# data_proV3.net
KiCad netlist of a schematic drawn in EAGLE
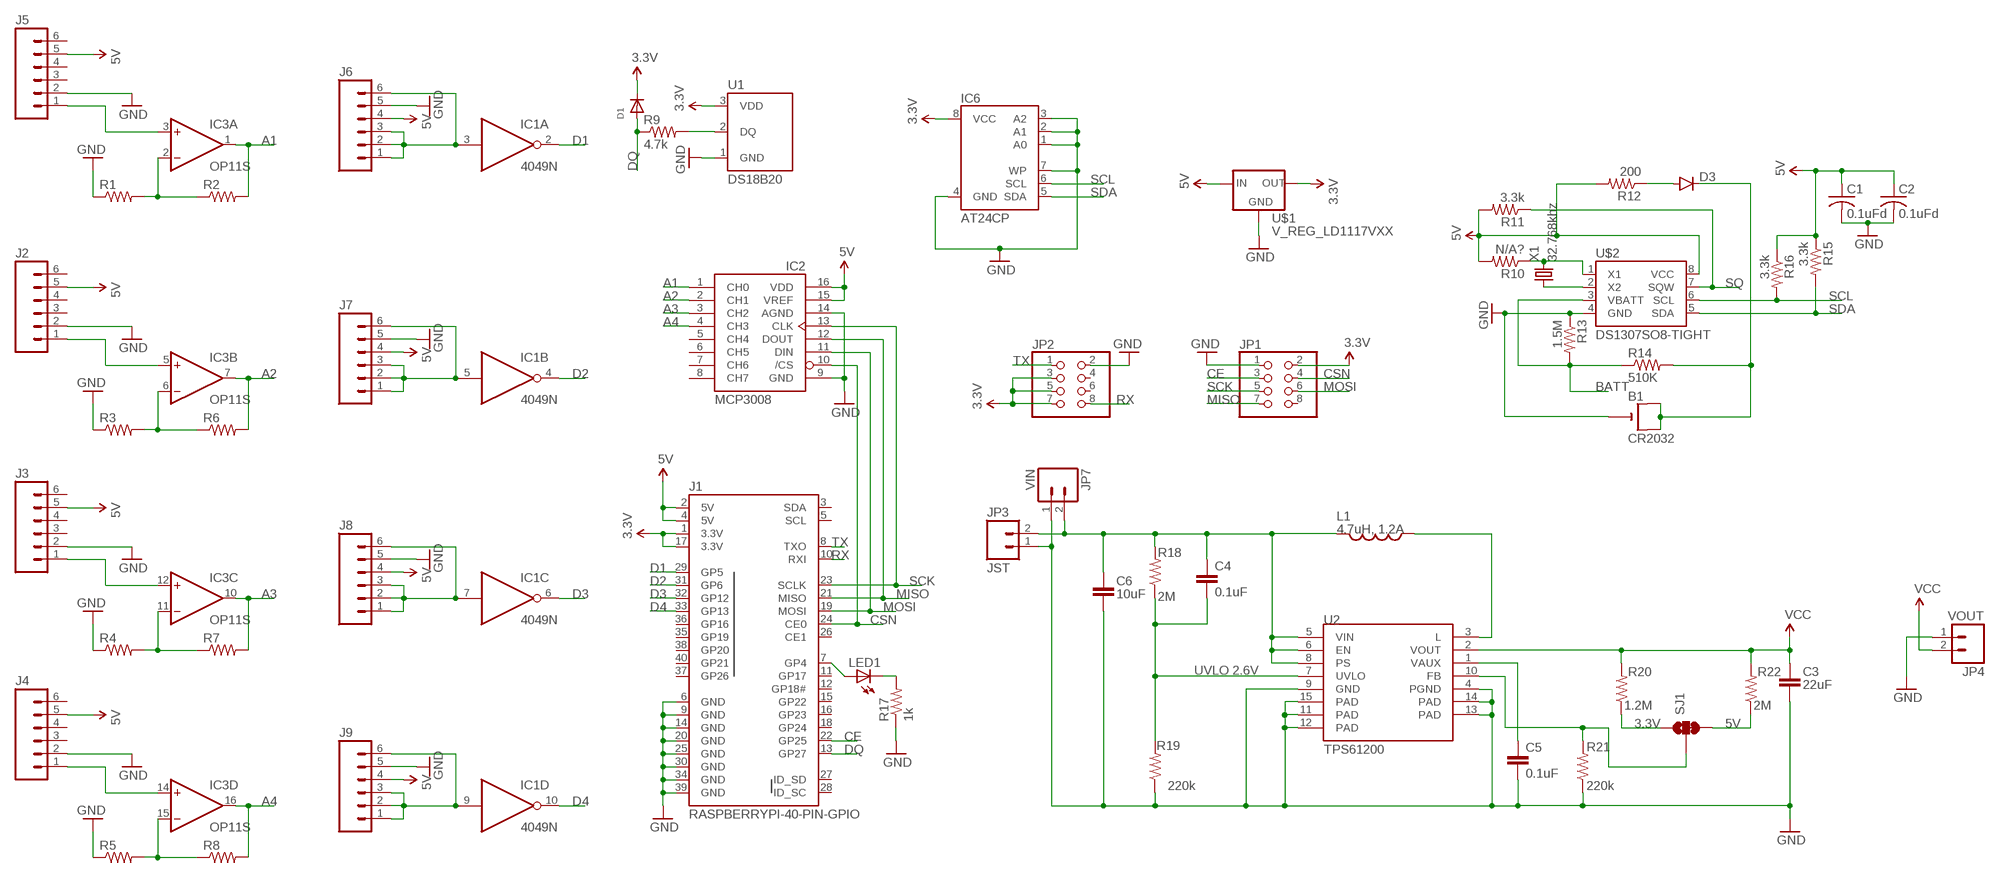
[diagram p0: schematic, sheet 1]

(export (version "E")
  (design (tool "Eeschema 10.0.6"))
  (components
    (comp (ref "B1")
      (value "CR2032")
      (footprint "eagle-import:CR2032-SMD")
      (libsource (lib "eagle-import") (part "CR2032SMT"))
    )
    (comp (ref "C1")
      (value "0.1uFd")
      (footprint "eagle-import:C0805")
      (libsource (lib "eagle-import") (part "C-USC0805"))
    )
    (comp (ref "C2")
      (value "0.1uFd")
      (footprint "eagle-import:C0805")
      (libsource (lib "eagle-import") (part "C-USC0805"))
    )
    (comp (ref "C3")
      (value "22uF")
      (footprint "eagle-import:0805")
      (libsource (lib "eagle-import") (part "CAP0805"))
    )
    (comp (ref "C4")
      (value "0.1uF")
      (footprint "eagle-import:0603-CAP")
      (libsource (lib "eagle-import") (part "CAP0603-CAP"))
    )
    (comp (ref "C5")
      (value "0.1uF")
      (footprint "eagle-import:0603-CAP")
      (libsource (lib "eagle-import") (part "CAP0603-CAP"))
    )
    (comp (ref "C6")
      (value "10uF")
      (footprint "eagle-import:1206")
      (libsource (lib "eagle-import") (part "CAP1206"))
    )
    (comp (ref "D1")
      (value "DIODESOD-323F")
      (footprint "eagle-import:SOD-323F")
      (libsource (lib "eagle-import") (part "DIODESOD-323F"))
    )
    (comp (ref "D3")
      (value "DIODESMB")
      (footprint "eagle-import:SMB-DIODE")
      (libsource (lib "eagle-import") (part "DIODESMB"))
    )
    (comp (ref "IC1")
      (value "4049N")
      (footprint "eagle-import:DIL16")
      (libsource (lib "eagle-import") (part "4049N"))
    )
    (comp (ref "IC2")
      (value "MCP3008")
      (footprint "eagle-import:DIL16")
      (libsource (lib "eagle-import") (part "MCP3008"))
    )
    (comp (ref "IC3")
      (value "OP11S")
      (footprint "eagle-import:DIL16")
      (libsource (lib "eagle-import") (part "OP11S"))
    )
    (comp (ref "IC6")
      (value "AT24CP")
      (footprint "eagle-import:DIL08")
      (fields (field (name "MPN") "AT24C1024BW-SH-B"))
      (libsource (lib "eagle-import") (part "AT24CP"))
    )
    (comp (ref "J1")
      (value "RASPBERRYPI-40-PIN-GPIO")
      (footprint "eagle-import:2X20-SHROUDED")
      (libsource (lib "eagle-import") (part "RASPBERRYPI-40-PIN-GPIO"))
    )
    (comp (ref "J2")
      (value "M06VERNIER-ANALOG")
      (footprint "eagle-import:BTA")
      (libsource (lib "eagle-import") (part "M06VERNIER-ANALOG"))
    )
    (comp (ref "J3")
      (value "M06VERNIER-ANALOG")
      (footprint "eagle-import:BTA")
      (libsource (lib "eagle-import") (part "M06VERNIER-ANALOG"))
    )
    (comp (ref "J4")
      (value "M06VERNIER-ANALOG")
      (footprint "eagle-import:BTA")
      (libsource (lib "eagle-import") (part "M06VERNIER-ANALOG"))
    )
    (comp (ref "J5")
      (value "M06VERNIER-ANALOG")
      (footprint "eagle-import:BTA")
      (libsource (lib "eagle-import") (part "M06VERNIER-ANALOG"))
    )
    (comp (ref "J6")
      (value "M06VERNIER-DIGITAL")
      (footprint "eagle-import:BTD")
      (libsource (lib "eagle-import") (part "M06VERNIER-DIGITAL"))
    )
    (comp (ref "J7")
      (value "M06VERNIER-DIGITAL")
      (footprint "eagle-import:BTD")
      (libsource (lib "eagle-import") (part "M06VERNIER-DIGITAL"))
    )
    (comp (ref "J8")
      (value "M06VERNIER-DIGITAL")
      (footprint "eagle-import:BTD")
      (libsource (lib "eagle-import") (part "M06VERNIER-DIGITAL"))
    )
    (comp (ref "J9")
      (value "M06VERNIER-DIGITAL")
      (footprint "eagle-import:BTD")
      (libsource (lib "eagle-import") (part "M06VERNIER-DIGITAL"))
    )
    (comp (ref "JP1")
      (value "PINHD-2X4")
      (footprint "eagle-import:2X04")
      (libsource (lib "eagle-import") (part "pinhead_PINHD-2X4"))
    )
    (comp (ref "JP2")
      (value "PINHD-2X4")
      (footprint "eagle-import:2X04")
      (libsource (lib "eagle-import") (part "PINHD-2X4"))
    )
    (comp (ref "JP3")
      (value "JST")
      (footprint "eagle-import:JST-2-SMD")
      (libsource (lib "eagle-import") (part "M02-JST-2MM-SMT"))
    )
    (comp (ref "JP4")
      (value "VOUT")
      (footprint "eagle-import:1X02")
      (libsource (lib "eagle-import") (part "M02PTH"))
    )
    (comp (ref "JP7")
      (value "VIN")
      (footprint "eagle-import:1X02")
      (libsource (lib "eagle-import") (part "M02PTH"))
    )
    (comp (ref "L1")
      (value "4.7uH, 1.2A")
      (footprint "eagle-import:CDRH2D09")
      (libsource (lib "eagle-import") (part "INDUCTOR."))
    )
    (comp (ref "LED1")
      (value "LEDCHIP-LED0805")
      (footprint "eagle-import:CHIP-LED0805")
      (libsource (lib "eagle-import") (part "LEDCHIP-LED0805"))
    )
    (comp (ref "R1")
      (value "R-US_R0805")
      (footprint "eagle-import:R0805")
      (libsource (lib "eagle-import") (part "resistor_R-US_R0805"))
    )
    (comp (ref "R2")
      (value "R-US_R0805")
      (footprint "eagle-import:R0805")
      (libsource (lib "eagle-import") (part "resistor_R-US_R0805"))
    )
    (comp (ref "R3")
      (value "R-US_R0805")
      (footprint "eagle-import:R0805")
      (libsource (lib "eagle-import") (part "resistor_R-US_R0805"))
    )
    (comp (ref "R4")
      (value "R-US_R0805")
      (footprint "eagle-import:R0805")
      (libsource (lib "eagle-import") (part "resistor_R-US_R0805"))
    )
    (comp (ref "R5")
      (value "R-US_R0805")
      (footprint "eagle-import:R0805")
      (libsource (lib "eagle-import") (part "resistor_R-US_R0805"))
    )
    (comp (ref "R6")
      (value "R-US_R0805")
      (footprint "eagle-import:R0805")
      (libsource (lib "eagle-import") (part "resistor_R-US_R0805"))
    )
    (comp (ref "R7")
      (value "R-US_R0805")
      (footprint "eagle-import:R0805")
      (libsource (lib "eagle-import") (part "resistor_R-US_R0805"))
    )
    (comp (ref "R8")
      (value "R-US_R0805")
      (footprint "eagle-import:R0805")
      (libsource (lib "eagle-import") (part "resistor_R-US_R0805"))
    )
    (comp (ref "R9")
      (value "4.7k")
      (footprint "eagle-import:R0805")
      (libsource (lib "eagle-import") (part "resistor_R-US_R0805"))
    )
    (comp (ref "R10")
      (value "N/A?")
      (footprint "eagle-import:R0805")
      (libsource (lib "eagle-import") (part "R-US_R0805"))
    )
    (comp (ref "R11")
      (value "3.3k")
      (footprint "eagle-import:R0805")
      (libsource (lib "eagle-import") (part "R-US_R0805"))
    )
    (comp (ref "R12")
      (value "200")
      (footprint "eagle-import:R0805")
      (libsource (lib "eagle-import") (part "R-US_R0805"))
    )
    (comp (ref "R13")
      (value "1.5M")
      (footprint "eagle-import:R0805")
      (libsource (lib "eagle-import") (part "R-US_R0805"))
    )
    (comp (ref "R14")
      (value "510K")
      (footprint "eagle-import:R0805")
      (libsource (lib "eagle-import") (part "R-US_R0805"))
    )
    (comp (ref "R15")
      (value "3.3k")
      (footprint "eagle-import:R0805")
      (libsource (lib "eagle-import") (part "R-US_R0805"))
    )
    (comp (ref "R16")
      (value "3.3k")
      (footprint "eagle-import:R0805")
      (libsource (lib "eagle-import") (part "R-US_R0805"))
    )
    (comp (ref "R17")
      (value "1k")
      (footprint "eagle-import:R0805")
      (libsource (lib "eagle-import") (part "R-US_R0805"))
    )
    (comp (ref "R18")
      (value "2M")
      (footprint "eagle-import:0603-RES")
      (libsource (lib "eagle-import") (part "RESISTOR0603-RES"))
    )
    (comp (ref "R19")
      (value "220k")
      (footprint "eagle-import:0603-RES")
      (libsource (lib "eagle-import") (part "RESISTOR0603-RES"))
    )
    (comp (ref "R20")
      (value "1.2M")
      (footprint "eagle-import:0603-RES")
      (libsource (lib "eagle-import") (part "RESISTOR0603-RES"))
    )
    (comp (ref "R21")
      (value "220k")
      (footprint "eagle-import:0603-RES")
      (libsource (lib "eagle-import") (part "RESISTOR0603-RES"))
    )
    (comp (ref "R22")
      (value "2M")
      (footprint "eagle-import:0603-RES")
      (libsource (lib "eagle-import") (part "RESISTOR0603-RES"))
    )
    (comp (ref "SJ1")
      (value "SOLDERJUMPER_2WAYPASTE2&3")
      (footprint "eagle-import:SJ_3_PASTE2&3")
      (libsource (lib "eagle-import") (part "SOLDERJUMPER_2WAYPASTE2&3"))
    )
    (comp (ref "U$1")
      (value "V_REG_LD1117VXX")
      (footprint "eagle-import:78XXL")
      (libsource (lib "eagle-import") (part "V_REG_LD1117VXX"))
    )
    (comp (ref "U$2")
      (value "DS1307SO8-TIGHT")
      (footprint "eagle-import:SO08-TIGHT")
      (libsource (lib "eagle-import") (part "DS1307SO8-TIGHT"))
    )
    (comp (ref "U1")
      (value "DS18B20")
      (footprint "eagle-import:TO-92-AMMO")
      (libsource (lib "eagle-import") (part "DS18B20"))
    )
    (comp (ref "U2")
      (value "TPS61200")
      (footprint "eagle-import:QFN-10_PAD")
      (libsource (lib "eagle-import") (part "TPS61200"))
    )
    (comp (ref "X1")
      (value "32.768khz")
      (footprint "eagle-import:TC38H")
      (libsource (lib "eagle-import") (part "CRYSTALTC38H"))
    )
  )
  (nets
    (net (code "1") (name "/A1") (class "Default")
      (node (ref "IC2") (pin "1") (pinfunction "CH0_1") (pintype "input"))
      (node (ref "IC3") (pin "1") (pinfunction "OUT_1") (pintype "output"))
      (node (ref "R2") (pin "2") (pinfunction "2_2") (pintype "passive"))
    )
    (net (code "2") (name "/A2") (class "Default")
      (node (ref "IC2") (pin "2") (pinfunction "CH1_2") (pintype "input"))
      (node (ref "IC3") (pin "7") (pinfunction "OUT_7") (pintype "output"))
      (node (ref "R6") (pin "2") (pinfunction "2_2") (pintype "passive"))
    )
    (net (code "3") (name "/A3") (class "Default")
      (node (ref "IC2") (pin "3") (pinfunction "CH2_3") (pintype "input"))
      (node (ref "IC3") (pin "10") (pinfunction "OUT_10") (pintype "output"))
      (node (ref "R7") (pin "2") (pinfunction "2_2") (pintype "passive"))
    )
    (net (code "4") (name "/A4") (class "Default")
      (node (ref "IC2") (pin "4") (pinfunction "CH3_4") (pintype "input"))
      (node (ref "IC3") (pin "16") (pinfunction "OUT_16") (pintype "output"))
      (node (ref "R8") (pin "2") (pinfunction "2_2") (pintype "passive"))
    )
    (net (code "5") (name "/BATT") (class "Default")
      (node (ref "R13") (pin "2") (pinfunction "2_2") (pintype "passive"))
      (node (ref "R14") (pin "1") (pinfunction "1_1") (pintype "passive"))
      (node (ref "U$2") (pin "3") (pinfunction "VBATT_3") (pintype "bidirectional"))
    )
    (net (code "6") (name "/CE") (class "Default")
      (node (ref "J1") (pin "22") (pinfunction "GP25_22") (pintype "bidirectional"))
      (node (ref "JP1") (pin "3") (pinfunction "3_3") (pintype "passive"))
    )
    (net (code "7") (name "/CSN") (class "Default")
      (node (ref "IC2") (pin "10") (pinfunction "/CS_10") (pintype "input"))
      (node (ref "J1") (pin "24") (pinfunction "CE0_24") (pintype "output"))
      (node (ref "JP1") (pin "4") (pinfunction "4_4") (pintype "passive"))
    )
    (net (code "8") (name "/D1") (class "Default")
      (node (ref "IC1") (pin "2") (pinfunction "O_2") (pintype "output"))
      (node (ref "J1") (pin "29") (pinfunction "GP5_29") (pintype "bidirectional"))
    )
    (net (code "9") (name "/D2") (class "Default")
      (node (ref "IC1") (pin "4") (pinfunction "O_4") (pintype "output"))
      (node (ref "J1") (pin "31") (pinfunction "GP6_31") (pintype "bidirectional"))
    )
    (net (code "10") (name "/D3") (class "Default")
      (node (ref "IC1") (pin "6") (pinfunction "O_6") (pintype "output"))
      (node (ref "J1") (pin "32") (pinfunction "GP12_32") (pintype "bidirectional"))
    )
    (net (code "11") (name "/D4") (class "Default")
      (node (ref "IC1") (pin "10") (pinfunction "O_10") (pintype "output"))
      (node (ref "J1") (pin "33") (pinfunction "GP13_33") (pintype "bidirectional"))
    )
    (net (code "12") (name "/DQ") (class "Default")
      (node (ref "D1") (pin "A") (pinfunction "A_A") (pintype "passive"))
      (node (ref "J1") (pin "13") (pinfunction "GP27_13") (pintype "bidirectional"))
      (node (ref "R9") (pin "1") (pinfunction "1_1") (pintype "passive"))
    )
    (net (code "13") (name "/MISO") (class "Default")
      (node (ref "IC2") (pin "12") (pinfunction "DOUT_12") (pintype "output"))
      (node (ref "J1") (pin "21") (pinfunction "MISO_21") (pintype "input"))
      (node (ref "JP1") (pin "7") (pinfunction "7_7") (pintype "passive"))
    )
    (net (code "14") (name "/MOSI") (class "Default")
      (node (ref "IC2") (pin "11") (pinfunction "DIN_11") (pintype "input"))
      (node (ref "J1") (pin "19") (pinfunction "MOSI_19") (pintype "output"))
      (node (ref "JP1") (pin "6") (pinfunction "6_6") (pintype "passive"))
    )
    (net (code "15") (name "/RX") (class "Default")
      (node (ref "J1") (pin "10") (pinfunction "RXI_10") (pintype "input"))
      (node (ref "JP2") (pin "8") (pinfunction "8_8") (pintype "passive"))
    )
    (net (code "16") (name "/SCK") (class "Default")
      (node (ref "IC2") (pin "13") (pinfunction "CLK_13") (pintype "input"))
      (node (ref "J1") (pin "23") (pinfunction "SCLK_23") (pintype "output"))
      (node (ref "JP1") (pin "5") (pinfunction "5_5") (pintype "passive"))
    )
    (net (code "17") (name "/SCL") (class "Default")
      (node (ref "IC6") (pin "6") (pinfunction "SCL_6") (pintype "bidirectional"))
      (node (ref "R16") (pin "2") (pinfunction "2_2") (pintype "passive"))
      (node (ref "U$2") (pin "6") (pinfunction "SCL_6") (pintype "bidirectional"))
    )
    (net (code "18") (name "/SDA") (class "Default")
      (node (ref "IC6") (pin "5") (pinfunction "SDA_5") (pintype "bidirectional"))
      (node (ref "R15") (pin "2") (pinfunction "2_2") (pintype "passive"))
      (node (ref "U$2") (pin "5") (pinfunction "SDA_5") (pintype "bidirectional"))
    )
    (net (code "19") (name "/SQ") (class "Default")
      (node (ref "R11") (pin "1") (pinfunction "1_1") (pintype "passive"))
      (node (ref "U$2") (pin "7") (pinfunction "SQW_7") (pintype "bidirectional"))
    )
    (net (code "20") (name "/TX") (class "Default")
      (node (ref "J1") (pin "8") (pinfunction "TXO_8") (pintype "output"))
      (node (ref "JP2") (pin "1") (pinfunction "1_1") (pintype "passive"))
    )
    (net (code "21") (name "3.3V") (class "Default")
      (node (ref "D1") (pin "C") (pinfunction "C_C") (pintype "passive"))
      (node (ref "IC6") (pin "8") (pinfunction "VCC_8") (pintype "power_in"))
      (node (ref "J1") (pin "1") (pinfunction "3.3V_1") (pintype "power_in"))
      (node (ref "J1") (pin "17") (pinfunction "3.3V_17") (pintype "power_in"))
      (node (ref "JP1") (pin "2") (pinfunction "2_2") (pintype "passive"))
      (node (ref "JP2") (pin "3") (pinfunction "3_3") (pintype "passive"))
      (node (ref "JP2") (pin "5") (pinfunction "5_5") (pintype "passive"))
      (node (ref "JP2") (pin "7") (pinfunction "7_7") (pintype "passive"))
      (node (ref "R20") (pin "1") (pinfunction "1_1") (pintype "passive"))
      (node (ref "SJ1") (pin "1") (pinfunction "1_1") (pintype "passive"))
      (node (ref "U$1") (pin "GND") (pinfunction "OUT_GND") (pintype "passive"))
      (node (ref "U1") (pin "3") (pinfunction "VDD_3") (pintype "power_in"))
    )
    (net (code "22") (name "5V") (class "Default")
      (node (ref "C1") (pin "1") (pinfunction "1_1") (pintype "passive"))
      (node (ref "C2") (pin "1") (pinfunction "1_1") (pintype "passive"))
      (node (ref "IC2") (pin "15") (pinfunction "VREF_15") (pintype "input"))
      (node (ref "IC2") (pin "16") (pinfunction "VDD_16") (pintype "power_in"))
      (node (ref "J1") (pin "2") (pinfunction "5V_2") (pintype "power_in"))
      (node (ref "J1") (pin "4") (pinfunction "5V_4") (pintype "power_in"))
      (node (ref "J2") (pin "5") (pinfunction "5_5") (pintype "passive"))
      (node (ref "J3") (pin "5") (pinfunction "5_5") (pintype "passive"))
      (node (ref "J4") (pin "5") (pinfunction "5_5") (pintype "passive"))
      (node (ref "J5") (pin "5") (pinfunction "5_5") (pintype "passive"))
      (node (ref "J6") (pin "4") (pinfunction "4_4") (pintype "passive"))
      (node (ref "J7") (pin "4") (pinfunction "4_4") (pintype "passive"))
      (node (ref "J8") (pin "4") (pinfunction "4_4") (pintype "passive"))
      (node (ref "J9") (pin "4") (pinfunction "4_4") (pintype "passive"))
      (node (ref "R10") (pin "2") (pinfunction "2_2") (pintype "passive"))
      (node (ref "R11") (pin "2") (pinfunction "2_2") (pintype "passive"))
      (node (ref "R12") (pin "2") (pinfunction "2_2") (pintype "passive"))
      (node (ref "R15") (pin "1") (pinfunction "1_1") (pintype "passive"))
      (node (ref "R16") (pin "1") (pinfunction "1_1") (pintype "passive"))
      (node (ref "R22") (pin "1") (pinfunction "1_1") (pintype "passive"))
      (node (ref "SJ1") (pin "3") (pinfunction "3_3") (pintype "passive"))
      (node (ref "U$1") (pin "OUT") (pinfunction "IN_OUT") (pintype "input"))
      (node (ref "U$2") (pin "8") (pinfunction "VCC_8") (pintype "bidirectional"))
    )
    (net (code "23") (name "GND") (class "Default")
      (node (ref "B1") (pin "-") (pinfunction "-_-") (pintype "passive"))
      (node (ref "C1") (pin "2") (pinfunction "2_2") (pintype "passive"))
      (node (ref "C2") (pin "2") (pinfunction "2_2") (pintype "passive"))
      (node (ref "C3") (pin "2") (pinfunction "2_2") (pintype "passive"))
      (node (ref "C5") (pin "2") (pinfunction "2_2") (pintype "passive"))
      (node (ref "C6") (pin "2") (pinfunction "2_2") (pintype "passive"))
      (node (ref "IC2") (pin "14") (pinfunction "AGND_14") (pintype "power_in"))
      (node (ref "IC2") (pin "9") (pinfunction "GND_9") (pintype "power_in"))
      (node (ref "IC6") (pin "1") (pinfunction "A0_1") (pintype "input"))
      (node (ref "IC6") (pin "2") (pinfunction "A1_2") (pintype "input"))
      (node (ref "IC6") (pin "3") (pinfunction "A2_3") (pintype "input"))
      (node (ref "IC6") (pin "4") (pinfunction "GND_4") (pintype "power_in"))
      (node (ref "IC6") (pin "7") (pinfunction "WP_7") (pintype "input"))
      (node (ref "J1") (pin "14") (pinfunction "GND_14") (pintype "power_in"))
      (node (ref "J1") (pin "20") (pinfunction "GND_20") (pintype "power_in"))
      (node (ref "J1") (pin "25") (pinfunction "GND_25") (pintype "power_in"))
      (node (ref "J1") (pin "30") (pinfunction "GND_30") (pintype "power_in"))
      (node (ref "J1") (pin "34") (pinfunction "GND_34") (pintype "power_in"))
      (node (ref "J1") (pin "39") (pinfunction "GND_39") (pintype "power_in"))
      (node (ref "J1") (pin "6") (pinfunction "GND_6") (pintype "power_in"))
      (node (ref "J1") (pin "9") (pinfunction "GND_9") (pintype "power_in"))
      (node (ref "J2") (pin "2") (pinfunction "2_2") (pintype "passive"))
      (node (ref "J3") (pin "2") (pinfunction "2_2") (pintype "passive"))
      (node (ref "J4") (pin "2") (pinfunction "2_2") (pintype "passive"))
      (node (ref "J5") (pin "2") (pinfunction "2_2") (pintype "passive"))
      (node (ref "J6") (pin "5") (pinfunction "5_5") (pintype "passive"))
      (node (ref "J7") (pin "5") (pinfunction "5_5") (pintype "passive"))
      (node (ref "J8") (pin "5") (pinfunction "5_5") (pintype "passive"))
      (node (ref "J9") (pin "5") (pinfunction "5_5") (pintype "passive"))
      (node (ref "JP1") (pin "1") (pinfunction "1_1") (pintype "passive"))
      (node (ref "JP2") (pin "2") (pinfunction "2_2") (pintype "passive"))
      (node (ref "JP3") (pin "1") (pinfunction "1_1") (pintype "passive"))
      (node (ref "JP4") (pin "1") (pinfunction "1_1") (pintype "passive"))
      (node (ref "JP7") (pin "1") (pinfunction "1_1") (pintype "passive"))
      (node (ref "R1") (pin "1") (pinfunction "1_1") (pintype "passive"))
      (node (ref "R13") (pin "1") (pinfunction "1_1") (pintype "passive"))
      (node (ref "R17") (pin "1") (pinfunction "1_1") (pintype "passive"))
      (node (ref "R19") (pin "1") (pinfunction "1_1") (pintype "passive"))
      (node (ref "R21") (pin "1") (pinfunction "1_1") (pintype "passive"))
      (node (ref "R3") (pin "1") (pinfunction "1_1") (pintype "passive"))
      (node (ref "R4") (pin "1") (pinfunction "1_1") (pintype "passive"))
      (node (ref "R5") (pin "1") (pinfunction "1_1") (pintype "passive"))
      (node (ref "U$1") (pin "IN") (pinfunction "GND_IN") (pintype "input"))
      (node (ref "U$2") (pin "4") (pinfunction "GND_4") (pintype "bidirectional"))
      (node (ref "U1") (pin "1") (pinfunction "GND_1") (pintype "power_in"))
      (node (ref "U2") (pin "11") (pinfunction "PAD_11") (pintype "power_in"))
      (node (ref "U2") (pin "12") (pinfunction "PAD_12") (pintype "power_in"))
      (node (ref "U2") (pin "13") (pinfunction "PAD_13") (pintype "power_in"))
      (node (ref "U2") (pin "14") (pinfunction "PAD_14") (pintype "power_in"))
      (node (ref "U2") (pin "15") (pinfunction "PAD_15") (pintype "power_in"))
      (node (ref "U2") (pin "4") (pinfunction "PGND_4") (pintype "power_in"))
      (node (ref "U2") (pin "9") (pinfunction "GND_9") (pintype "power_in"))
    )
    (net (code "24") (name "Net-(B1-+)") (class "Default")
      (node (ref "B1") (pin "+$1") (pinfunction "+_+$1") (pintype "passive"))
      (node (ref "B1") (pin "+$2") (pinfunction "+1_+$2") (pintype "passive"))
      (node (ref "D3") (pin "C") (pinfunction "C_C") (pintype "passive"))
      (node (ref "R14") (pin "2") (pinfunction "2_2") (pintype "passive"))
    )
    (net (code "25") (name "Net-(D3-PadA)") (class "Default")
      (node (ref "D3") (pin "A") (pinfunction "A_A") (pintype "passive"))
      (node (ref "R12") (pin "1") (pinfunction "1_1") (pintype "passive"))
    )
    (net (code "26") (name "Net-(IC1A-I)") (class "Default")
      (node (ref "IC1") (pin "3") (pinfunction "I_3") (pintype "input"))
      (node (ref "J6") (pin "1") (pinfunction "1_1") (pintype "passive"))
      (node (ref "J6") (pin "2") (pinfunction "2_2") (pintype "passive"))
      (node (ref "J6") (pin "3") (pinfunction "3_3") (pintype "passive"))
      (node (ref "J6") (pin "6") (pinfunction "6_6") (pintype "passive"))
    )
    (net (code "27") (name "Net-(IC1B-I)") (class "Default")
      (node (ref "IC1") (pin "5") (pinfunction "I_5") (pintype "input"))
      (node (ref "J7") (pin "1") (pinfunction "1_1") (pintype "passive"))
      (node (ref "J7") (pin "2") (pinfunction "2_2") (pintype "passive"))
      (node (ref "J7") (pin "3") (pinfunction "3_3") (pintype "passive"))
      (node (ref "J7") (pin "6") (pinfunction "6_6") (pintype "passive"))
    )
    (net (code "28") (name "Net-(IC1C-I)") (class "Default")
      (node (ref "IC1") (pin "7") (pinfunction "I_7") (pintype "input"))
      (node (ref "J8") (pin "1") (pinfunction "1_1") (pintype "passive"))
      (node (ref "J8") (pin "2") (pinfunction "2_2") (pintype "passive"))
      (node (ref "J8") (pin "3") (pinfunction "3_3") (pintype "passive"))
      (node (ref "J8") (pin "6") (pinfunction "6_6") (pintype "passive"))
    )
    (net (code "29") (name "Net-(IC1D-I)") (class "Default")
      (node (ref "IC1") (pin "9") (pinfunction "I_9") (pintype "input"))
      (node (ref "J9") (pin "1") (pinfunction "1_1") (pintype "passive"))
      (node (ref "J9") (pin "2") (pinfunction "2_2") (pintype "passive"))
      (node (ref "J9") (pin "3") (pinfunction "3_3") (pintype "passive"))
      (node (ref "J9") (pin "6") (pinfunction "6_6") (pintype "passive"))
    )
    (net (code "30") (name "Net-(IC3A-+IN)") (class "Default")
      (node (ref "IC3") (pin "3") (pinfunction "+IN_3") (pintype "input"))
      (node (ref "J5") (pin "1") (pinfunction "1_1") (pintype "passive"))
    )
    (net (code "31") (name "Net-(IC3A--IN)") (class "Default")
      (node (ref "IC3") (pin "2") (pinfunction "-IN_2") (pintype "input"))
      (node (ref "R1") (pin "2") (pinfunction "2_2") (pintype "passive"))
      (node (ref "R2") (pin "1") (pinfunction "1_1") (pintype "passive"))
    )
    (net (code "32") (name "Net-(IC3B-+IN)") (class "Default")
      (node (ref "IC3") (pin "5") (pinfunction "+IN_5") (pintype "input"))
      (node (ref "J2") (pin "1") (pinfunction "1_1") (pintype "passive"))
    )
    (net (code "33") (name "Net-(IC3B--IN)") (class "Default")
      (node (ref "IC3") (pin "6") (pinfunction "-IN_6") (pintype "input"))
      (node (ref "R3") (pin "2") (pinfunction "2_2") (pintype "passive"))
      (node (ref "R6") (pin "1") (pinfunction "1_1") (pintype "passive"))
    )
    (net (code "34") (name "Net-(IC3C-+IN)") (class "Default")
      (node (ref "IC3") (pin "12") (pinfunction "+IN_12") (pintype "input"))
      (node (ref "J3") (pin "1") (pinfunction "1_1") (pintype "passive"))
    )
    (net (code "35") (name "Net-(IC3C--IN)") (class "Default")
      (node (ref "IC3") (pin "11") (pinfunction "-IN_11") (pintype "input"))
      (node (ref "R4") (pin "2") (pinfunction "2_2") (pintype "passive"))
      (node (ref "R7") (pin "1") (pinfunction "1_1") (pintype "passive"))
    )
    (net (code "36") (name "Net-(IC3D-+IN)") (class "Default")
      (node (ref "IC3") (pin "14") (pinfunction "+IN_14") (pintype "input"))
      (node (ref "J4") (pin "1") (pinfunction "1_1") (pintype "passive"))
    )
    (net (code "37") (name "Net-(IC3D--IN)") (class "Default")
      (node (ref "IC3") (pin "15") (pinfunction "-IN_15") (pintype "input"))
      (node (ref "R5") (pin "2") (pinfunction "2_2") (pintype "passive"))
      (node (ref "R8") (pin "1") (pinfunction "1_1") (pintype "passive"))
    )
    (net (code "38") (name "Net-(J1-GP4)") (class "Default")
      (node (ref "J1") (pin "7") (pinfunction "GP4_7") (pintype "bidirectional"))
      (node (ref "LED1") (pin "A") (pinfunction "A_A") (pintype "passive"))
    )
    (net (code "39") (name "Net-(L1-1)") (class "Default")
      (node (ref "L1") (pin "P$1") (pinfunction "1_P$1") (pintype "passive"))
      (node (ref "U2") (pin "3") (pinfunction "L_3") (pintype "passive"))
    )
    (net (code "40") (name "Net-(L1-2)") (class "Default")
      (node (ref "C4") (pin "1") (pinfunction "1_1") (pintype "passive"))
      (node (ref "C6") (pin "1") (pinfunction "1_1") (pintype "passive"))
      (node (ref "JP3") (pin "2") (pinfunction "2_2") (pintype "passive"))
      (node (ref "JP7") (pin "2") (pinfunction "2_2") (pintype "passive"))
      (node (ref "L1") (pin "P$2") (pinfunction "2_P$2") (pintype "passive"))
      (node (ref "R18") (pin "2") (pinfunction "2_2") (pintype "passive"))
      (node (ref "U2") (pin "5") (pinfunction "VIN_5") (pintype "power_in"))
      (node (ref "U2") (pin "6") (pinfunction "EN_6") (pintype "input"))
      (node (ref "U2") (pin "8") (pinfunction "PS_8") (pintype "input"))
    )
    (net (code "41") (name "Net-(LED1-PadC)") (class "Default")
      (node (ref "LED1") (pin "C") (pinfunction "C_C") (pintype "passive"))
      (node (ref "R17") (pin "2") (pinfunction "2_2") (pintype "passive"))
    )
    (net (code "42") (name "Net-(U$2-X1)") (class "Default")
      (node (ref "R10") (pin "1") (pinfunction "1_1") (pintype "passive"))
      (node (ref "U$2") (pin "1") (pinfunction "X1_1") (pintype "bidirectional"))
      (node (ref "X1") (pin "2") (pinfunction "2_2") (pintype "passive"))
    )
    (net (code "43") (name "Net-(U$2-X2)") (class "Default")
      (node (ref "U$2") (pin "2") (pinfunction "X2_2") (pintype "bidirectional"))
      (node (ref "X1") (pin "1") (pinfunction "1_1") (pintype "passive"))
    )
    (net (code "44") (name "Net-(U1-DQ)") (class "Default")
      (node (ref "R9") (pin "2") (pinfunction "2_2") (pintype "passive"))
      (node (ref "U1") (pin "2") (pinfunction "DQ_2") (pintype "bidirectional"))
    )
    (net (code "45") (name "Net-(U2-FB)") (class "Default")
      (node (ref "R21") (pin "2") (pinfunction "2_2") (pintype "passive"))
      (node (ref "SJ1") (pin "2") (pinfunction "2_2") (pintype "passive"))
      (node (ref "U2") (pin "10") (pinfunction "FB_10") (pintype "passive"))
    )
    (net (code "46") (name "Net-(U2-UVLO)") (class "Default")
      (node (ref "C4") (pin "2") (pinfunction "2_2") (pintype "passive"))
      (node (ref "R18") (pin "1") (pinfunction "1_1") (pintype "passive"))
      (node (ref "R19") (pin "2") (pinfunction "2_2") (pintype "passive"))
      (node (ref "U2") (pin "7") (pinfunction "UVLO_7") (pintype "passive"))
    )
    (net (code "47") (name "Net-(U2-VAUX)") (class "Default")
      (node (ref "C5") (pin "1") (pinfunction "1_1") (pintype "passive"))
      (node (ref "U2") (pin "1") (pinfunction "VAUX_1") (pintype "passive"))
    )
    (net (code "48") (name "VCC") (class "Default")
      (node (ref "C3") (pin "1") (pinfunction "1_1") (pintype "passive"))
      (node (ref "JP4") (pin "2") (pinfunction "2_2") (pintype "passive"))
      (node (ref "R20") (pin "2") (pinfunction "2_2") (pintype "passive"))
      (node (ref "R22") (pin "2") (pinfunction "2_2") (pintype "passive"))
      (node (ref "U2") (pin "2") (pinfunction "VOUT_2") (pintype "passive"))
    )
    (net (code "49") (name "unconnected-(IC2-CH4-Pad5)") (class "Default")
      (node (ref "IC2") (pin "5") (pinfunction "CH4_5") (pintype "input"))
    )
    (net (code "50") (name "unconnected-(IC2-CH5-Pad6)") (class "Default")
      (node (ref "IC2") (pin "6") (pinfunction "CH5_6") (pintype "input"))
    )
    (net (code "51") (name "unconnected-(IC2-CH6-Pad7)") (class "Default")
      (node (ref "IC2") (pin "7") (pinfunction "CH6_7") (pintype "input"))
    )
    (net (code "52") (name "unconnected-(IC2-CH7-Pad8)") (class "Default")
      (node (ref "IC2") (pin "8") (pinfunction "CH7_8") (pintype "input"))
    )
    (net (code "53") (name "unconnected-(J1-CE1-Pad26)") (class "Default")
      (node (ref "J1") (pin "26") (pinfunction "CE1_26") (pintype "output"))
    )
    (net (code "54") (name "unconnected-(J1-GP16-Pad36)") (class "Default")
      (node (ref "J1") (pin "36") (pinfunction "GP16_36") (pintype "bidirectional"))
    )
    (net (code "55") (name "unconnected-(J1-GP17-Pad11)") (class "Default")
      (node (ref "J1") (pin "11") (pinfunction "GP17_11") (pintype "bidirectional"))
    )
    (net (code "56") (name "unconnected-(J1-GP18#-Pad12)") (class "Default")
      (node (ref "J1") (pin "12") (pinfunction "GP18#_12") (pintype "bidirectional"))
    )
    (net (code "57") (name "unconnected-(J1-GP19-Pad35)") (class "Default")
      (node (ref "J1") (pin "35") (pinfunction "GP19_35") (pintype "bidirectional"))
    )
    (net (code "58") (name "unconnected-(J1-GP20-Pad38)") (class "Default")
      (node (ref "J1") (pin "38") (pinfunction "GP20_38") (pintype "bidirectional"))
    )
    (net (code "59") (name "unconnected-(J1-GP21-Pad40)") (class "Default")
      (node (ref "J1") (pin "40") (pinfunction "GP21_40") (pintype "bidirectional"))
    )
    (net (code "60") (name "unconnected-(J1-GP22-Pad15)") (class "Default")
      (node (ref "J1") (pin "15") (pinfunction "GP22_15") (pintype "bidirectional"))
    )
    (net (code "61") (name "unconnected-(J1-GP23-Pad16)") (class "Default")
      (node (ref "J1") (pin "16") (pinfunction "GP23_16") (pintype "bidirectional"))
    )
    (net (code "62") (name "unconnected-(J1-GP24-Pad18)") (class "Default")
      (node (ref "J1") (pin "18") (pinfunction "GP24_18") (pintype "bidirectional"))
    )
    (net (code "63") (name "unconnected-(J1-GP26-Pad37)") (class "Default")
      (node (ref "J1") (pin "37") (pinfunction "GP26_37") (pintype "bidirectional"))
    )
    (net (code "64") (name "unconnected-(J1-ID_SC-Pad28)") (class "Default")
      (node (ref "J1") (pin "28") (pinfunction "ID_SC_28") (pintype "bidirectional"))
    )
    (net (code "65") (name "unconnected-(J1-ID_SD-Pad27)") (class "Default")
      (node (ref "J1") (pin "27") (pinfunction "ID_SD_27") (pintype "bidirectional"))
    )
    (net (code "66") (name "unconnected-(J1-SCL-Pad5)") (class "Default")
      (node (ref "J1") (pin "5") (pinfunction "SCL_5") (pintype "bidirectional"))
    )
    (net (code "67") (name "unconnected-(J1-SDA-Pad3)") (class "Default")
      (node (ref "J1") (pin "3") (pinfunction "SDA_3") (pintype "bidirectional"))
    )
    (net (code "68") (name "unconnected-(J2-Pad3)") (class "Default")
      (node (ref "J2") (pin "3") (pinfunction "3_3") (pintype "passive"))
    )
    (net (code "69") (name "unconnected-(J2-Pad4)") (class "Default")
      (node (ref "J2") (pin "4") (pinfunction "4_4") (pintype "passive"))
    )
    (net (code "70") (name "unconnected-(J2-Pad6)") (class "Default")
      (node (ref "J2") (pin "6") (pinfunction "6_6") (pintype "passive"))
    )
    (net (code "71") (name "unconnected-(J3-Pad3)") (class "Default")
      (node (ref "J3") (pin "3") (pinfunction "3_3") (pintype "passive"))
    )
    (net (code "72") (name "unconnected-(J3-Pad4)") (class "Default")
      (node (ref "J3") (pin "4") (pinfunction "4_4") (pintype "passive"))
    )
    (net (code "73") (name "unconnected-(J3-Pad6)") (class "Default")
      (node (ref "J3") (pin "6") (pinfunction "6_6") (pintype "passive"))
    )
    (net (code "74") (name "unconnected-(J4-Pad3)") (class "Default")
      (node (ref "J4") (pin "3") (pinfunction "3_3") (pintype "passive"))
    )
    (net (code "75") (name "unconnected-(J4-Pad4)") (class "Default")
      (node (ref "J4") (pin "4") (pinfunction "4_4") (pintype "passive"))
    )
    (net (code "76") (name "unconnected-(J4-Pad6)") (class "Default")
      (node (ref "J4") (pin "6") (pinfunction "6_6") (pintype "passive"))
    )
    (net (code "77") (name "unconnected-(J5-Pad3)") (class "Default")
      (node (ref "J5") (pin "3") (pinfunction "3_3") (pintype "passive"))
    )
    (net (code "78") (name "unconnected-(J5-Pad4)") (class "Default")
      (node (ref "J5") (pin "4") (pinfunction "4_4") (pintype "passive"))
    )
    (net (code "79") (name "unconnected-(J5-Pad6)") (class "Default")
      (node (ref "J5") (pin "6") (pinfunction "6_6") (pintype "passive"))
    )
    (net (code "80") (name "unconnected-(JP1-Pad8)") (class "Default")
      (node (ref "JP1") (pin "8") (pinfunction "8_8") (pintype "passive"))
    )
    (net (code "81") (name "unconnected-(JP2-Pad4)") (class "Default")
      (node (ref "JP2") (pin "4") (pinfunction "4_4") (pintype "passive"))
    )
    (net (code "82") (name "unconnected-(JP2-Pad6)") (class "Default")
      (node (ref "JP2") (pin "6") (pinfunction "6_6") (pintype "passive"))
    )
  )
)
